# SCH_Octacon_Pico2.net
KiCad netlist of a schematic drawn in EasyEDA
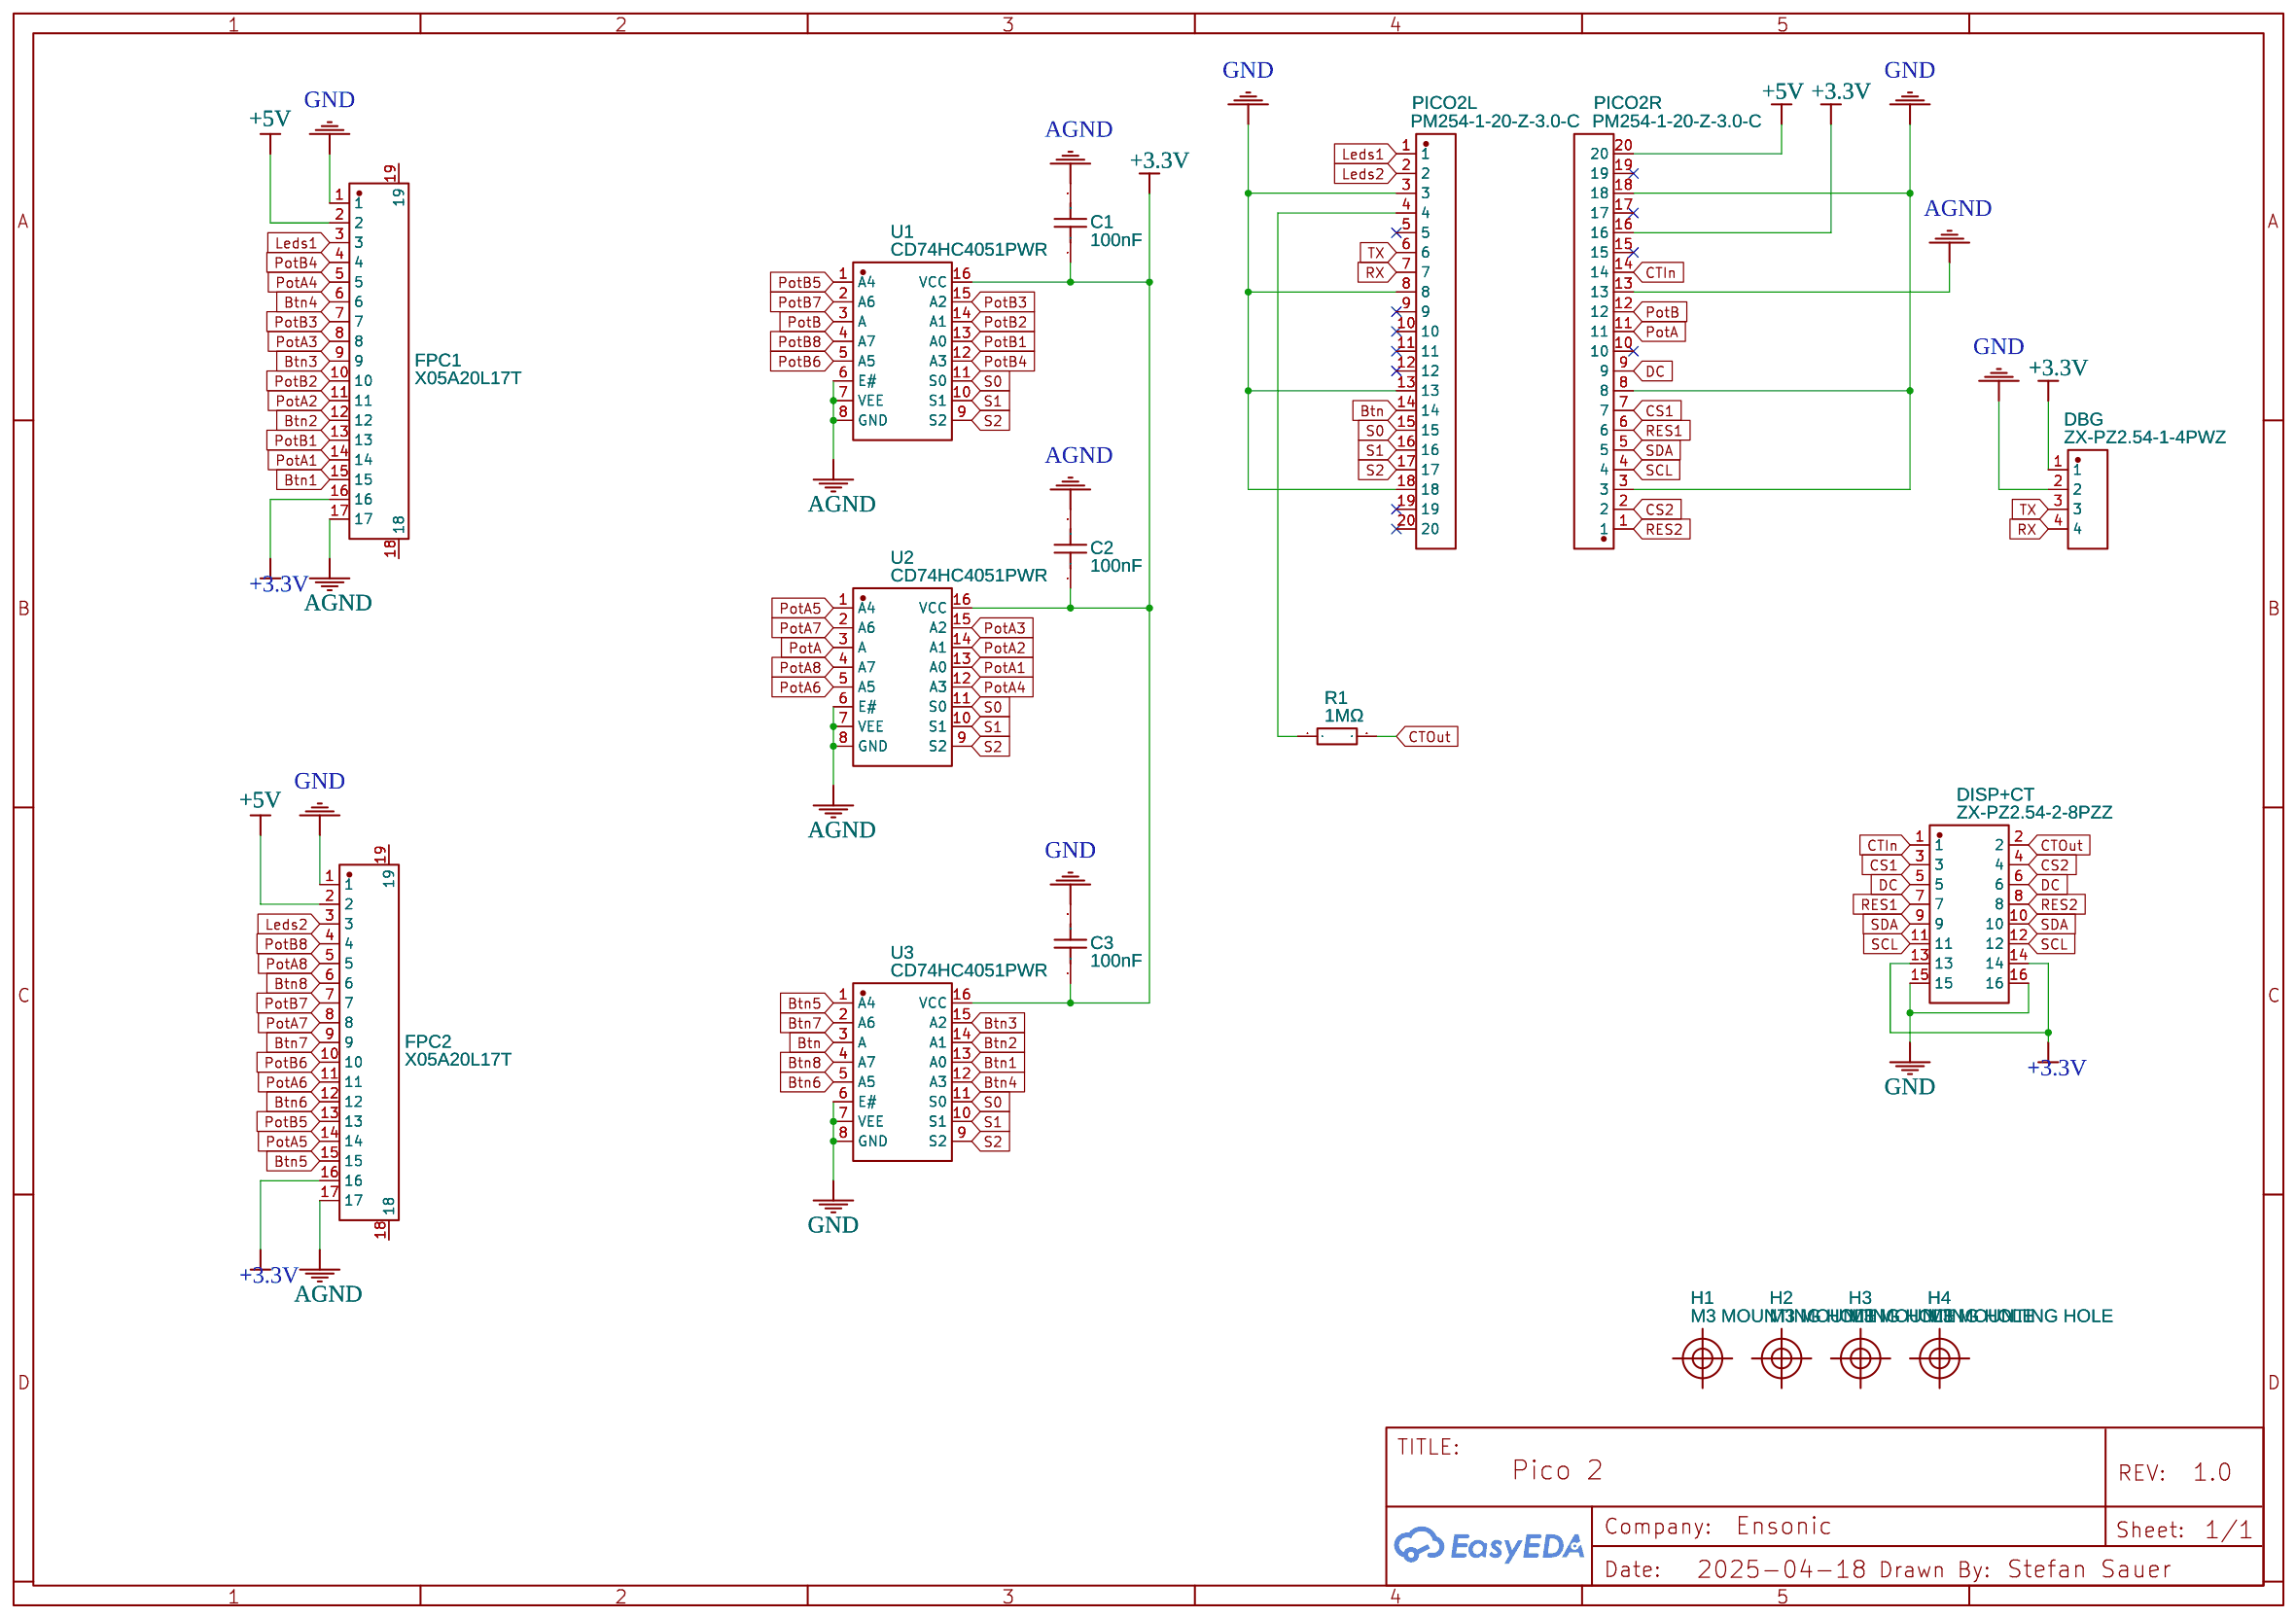
[diagram p0: schematic sheet]

(export (version "E")
  (design (tool "Eeschema 10.0.6"))
  (components
    (comp (ref "C1")
      (value "100nF")
      (fields
        (field (name "Manufacturer Part") "CT41G-0402-2X1-16V-0.1μF-K(N)")
        (field (name "Manufacturer") "TORCH(火炬)")
      )
      (libsource (lib "") (part "CT41G-0402-2X1-16V-0.1μF-K(N)"))
    )
    (comp (ref "C2")
      (value "100nF")
      (fields
        (field (name "Manufacturer Part") "CT41G-0402-2X1-16V-0.1μF-K(N)")
        (field (name "Manufacturer") "TORCH(火炬)")
      )
      (libsource (lib "") (part "CT41G-0402-2X1-16V-0.1μF-K(N)"))
    )
    (comp (ref "C3")
      (value "100nF")
      (fields
        (field (name "Manufacturer Part") "CT41G-0402-2X1-16V-0.1μF-K(N)")
        (field (name "Manufacturer") "TORCH(火炬)")
      )
      (libsource (lib "") (part "CT41G-0402-2X1-16V-0.1μF-K(N)"))
    )
    (comp (ref "DBG")
      (value "ZX-PZ2.54-1-4PWZ")
      (fields (field (name "Manufacturer") "Megastar(兆星)"))
      (libsource (lib "") (part "ZX-PZ2.54-1-4PWZ"))
    )
    (comp (ref "DISP+CT")
      (value "ZX-PZ2.54-2-8PZZ")
      (fields (field (name "Manufacturer") "Megastar(兆星)"))
      (libsource (lib "") (part "ZX-PZ2.54-2-8PZZ"))
    )
    (comp (ref "FPC1")
      (value "X05A20L17T")
      (fields (field (name "Manufacturer") "XKB Connection(中国星坤)"))
      (libsource (lib "") (part "X05A20L17T"))
    )
    (comp (ref "FPC2")
      (value "X05A20L17T")
      (fields (field (name "Manufacturer") "XKB Connection(中国星坤)"))
      (libsource (lib "") (part "X05A20L17T"))
    )
    (comp (ref "H1")
      (value "M3 MOUNTING HOLE")
      (fields (field (name "Manufacturer Part") "M3 Mounting Hole"))
      (libsource (lib "") (part "M3 MOUNTING HOLE"))
    )
    (comp (ref "H2")
      (value "M3 MOUNTING HOLE")
      (fields (field (name "Manufacturer Part") "M3 Mounting Hole"))
      (libsource (lib "") (part "M3 MOUNTING HOLE"))
    )
    (comp (ref "H3")
      (value "M3 MOUNTING HOLE")
      (fields (field (name "Manufacturer Part") "M3 Mounting Hole"))
      (libsource (lib "") (part "M3 MOUNTING HOLE"))
    )
    (comp (ref "H4")
      (value "M3 MOUNTING HOLE")
      (fields (field (name "Manufacturer Part") "M3 Mounting Hole"))
      (libsource (lib "") (part "M3 MOUNTING HOLE"))
    )
    (comp (ref "PICO2L")
      (value "PM254-1-20-Z-3.0-C")
      (fields (field (name "Manufacturer") "HCTL(华灿天禄)"))
      (libsource (lib "") (part "PM254-1-20-Z-3.0-C_1"))
    )
    (comp (ref "PICO2R")
      (value "PM254-1-20-Z-3.0-C")
      (fields (field (name "Manufacturer") "HCTL(华灿天禄)"))
      (libsource (lib "") (part "PM254-1-20-Z-3.0-C"))
    )
    (comp (ref "R1")
      (value "1MΩ")
      (fields
        (field (name "Manufacturer Part") "0805W8F1004T5E")
        (field (name "Manufacturer") "UNI-ROYAL(厚声)")
      )
      (libsource (lib "") (part "0805W8F1004T5E"))
    )
    (comp (ref "U1")
      (value "CD74HC4051PWR")
      (fields (field (name "Manufacturer") "TI(德州仪器)"))
      (libsource (lib "") (part "CD74HC4051PWR"))
    )
    (comp (ref "U2")
      (value "CD74HC4051PWR")
      (fields (field (name "Manufacturer") "TI(德州仪器)"))
      (libsource (lib "") (part "CD74HC4051PWR"))
    )
    (comp (ref "U3")
      (value "CD74HC4051PWR")
      (fields (field (name "Manufacturer") "TI(德州仪器)"))
      (libsource (lib "") (part "CD74HC4051PWR"))
    )
  )
  (nets
    (net (code "1") (name "+3.3V") (class "Default")
      (node (ref "C1") (pin "1") (pinfunction "1_1") (pintype "unspecified"))
      (node (ref "C2") (pin "1") (pinfunction "1_1") (pintype "unspecified"))
      (node (ref "C3") (pin "1") (pinfunction "1_1") (pintype "unspecified"))
      (node (ref "DBG") (pin "1") (pinfunction "1_1") (pintype "unspecified"))
      (node (ref "DISP+CT") (pin "13") (pinfunction "13_13") (pintype "unspecified"))
      (node (ref "DISP+CT") (pin "14") (pinfunction "14_14") (pintype "unspecified"))
      (node (ref "FPC1") (pin "16") (pinfunction "16_16") (pintype "unspecified"))
      (node (ref "FPC2") (pin "16") (pinfunction "16_16") (pintype "unspecified"))
      (node (ref "PICO2R") (pin "16") (pinfunction "16_16") (pintype "unspecified"))
      (node (ref "U1") (pin "16") (pinfunction "VCC_16") (pintype "unspecified"))
      (node (ref "U2") (pin "16") (pinfunction "VCC_16") (pintype "unspecified"))
      (node (ref "U3") (pin "16") (pinfunction "VCC_16") (pintype "unspecified"))
    )
    (net (code "2") (name "+5V") (class "Default")
      (node (ref "FPC1") (pin "2") (pinfunction "2_2") (pintype "unspecified"))
      (node (ref "FPC2") (pin "2") (pinfunction "2_2") (pintype "unspecified"))
      (node (ref "PICO2R") (pin "20") (pinfunction "20_20") (pintype "unspecified"))
    )
    (net (code "3") (name "AGND") (class "Default")
      (node (ref "C1") (pin "2") (pinfunction "2_2") (pintype "unspecified"))
      (node (ref "C2") (pin "2") (pinfunction "2_2") (pintype "unspecified"))
      (node (ref "FPC1") (pin "17") (pinfunction "17_17") (pintype "unspecified"))
      (node (ref "FPC2") (pin "17") (pinfunction "17_17") (pintype "unspecified"))
      (node (ref "PICO2R") (pin "13") (pinfunction "13_13") (pintype "unspecified"))
      (node (ref "U1") (pin "6") (pinfunction "E#_6") (pintype "unspecified"))
      (node (ref "U1") (pin "7") (pinfunction "VEE_7") (pintype "unspecified"))
      (node (ref "U1") (pin "8") (pinfunction "GND_8") (pintype "unspecified"))
      (node (ref "U2") (pin "6") (pinfunction "E#_6") (pintype "unspecified"))
      (node (ref "U2") (pin "7") (pinfunction "VEE_7") (pintype "unspecified"))
      (node (ref "U2") (pin "8") (pinfunction "GND_8") (pintype "unspecified"))
    )
    (net (code "4") (name "Btn") (class "Default")
      (node (ref "PICO2L") (pin "14") (pinfunction "14_14") (pintype "unspecified"))
      (node (ref "U3") (pin "3") (pinfunction "A_3") (pintype "unspecified"))
    )
    (net (code "5") (name "Btn1") (class "Default")
      (node (ref "FPC1") (pin "15") (pinfunction "15_15") (pintype "unspecified"))
      (node (ref "U3") (pin "13") (pinfunction "A0_13") (pintype "unspecified"))
    )
    (net (code "6") (name "Btn2") (class "Default")
      (node (ref "FPC1") (pin "12") (pinfunction "12_12") (pintype "unspecified"))
      (node (ref "U3") (pin "14") (pinfunction "A1_14") (pintype "unspecified"))
    )
    (net (code "7") (name "Btn3") (class "Default")
      (node (ref "FPC1") (pin "9") (pinfunction "9_9") (pintype "unspecified"))
      (node (ref "U3") (pin "15") (pinfunction "A2_15") (pintype "unspecified"))
    )
    (net (code "8") (name "Btn4") (class "Default")
      (node (ref "FPC1") (pin "6") (pinfunction "6_6") (pintype "unspecified"))
      (node (ref "U3") (pin "12") (pinfunction "A3_12") (pintype "unspecified"))
    )
    (net (code "9") (name "Btn5") (class "Default")
      (node (ref "FPC2") (pin "15") (pinfunction "15_15") (pintype "unspecified"))
      (node (ref "U3") (pin "1") (pinfunction "A4_1") (pintype "unspecified"))
    )
    (net (code "10") (name "Btn6") (class "Default")
      (node (ref "FPC2") (pin "12") (pinfunction "12_12") (pintype "unspecified"))
      (node (ref "U3") (pin "5") (pinfunction "A5_5") (pintype "unspecified"))
    )
    (net (code "11") (name "Btn7") (class "Default")
      (node (ref "FPC2") (pin "9") (pinfunction "9_9") (pintype "unspecified"))
      (node (ref "U3") (pin "2") (pinfunction "A6_2") (pintype "unspecified"))
    )
    (net (code "12") (name "Btn8") (class "Default")
      (node (ref "FPC2") (pin "6") (pinfunction "6_6") (pintype "unspecified"))
      (node (ref "U3") (pin "4") (pinfunction "A7_4") (pintype "unspecified"))
    )
    (net (code "13") (name "CS1") (class "Default")
      (node (ref "DISP+CT") (pin "3") (pinfunction "3_3") (pintype "unspecified"))
      (node (ref "PICO2R") (pin "7") (pinfunction "7_7") (pintype "unspecified"))
    )
    (net (code "14") (name "CS2") (class "Default")
      (node (ref "DISP+CT") (pin "4") (pinfunction "4_4") (pintype "unspecified"))
      (node (ref "PICO2R") (pin "2") (pinfunction "2_2") (pintype "unspecified"))
    )
    (net (code "15") (name "CTIn") (class "Default")
      (node (ref "DISP+CT") (pin "1") (pinfunction "1_1") (pintype "unspecified"))
      (node (ref "PICO2R") (pin "14") (pinfunction "14_14") (pintype "unspecified"))
    )
    (net (code "16") (name "CTOut") (class "Default")
      (node (ref "DISP+CT") (pin "2") (pinfunction "2_2") (pintype "unspecified"))
      (node (ref "R1") (pin "2") (pinfunction "2_2") (pintype "input"))
    )
    (net (code "17") (name "DC") (class "Default")
      (node (ref "DISP+CT") (pin "5") (pinfunction "5_5") (pintype "unspecified"))
      (node (ref "DISP+CT") (pin "6") (pinfunction "6_6") (pintype "unspecified"))
      (node (ref "PICO2R") (pin "9") (pinfunction "9_9") (pintype "unspecified"))
    )
    (net (code "18") (name "GND") (class "Default")
      (node (ref "C3") (pin "2") (pinfunction "2_2") (pintype "unspecified"))
      (node (ref "DBG") (pin "2") (pinfunction "2_2") (pintype "unspecified"))
      (node (ref "DISP+CT") (pin "15") (pinfunction "15_15") (pintype "unspecified"))
      (node (ref "DISP+CT") (pin "16") (pinfunction "16_16") (pintype "unspecified"))
      (node (ref "FPC1") (pin "1") (pinfunction "1_1") (pintype "unspecified"))
      (node (ref "FPC2") (pin "1") (pinfunction "1_1") (pintype "unspecified"))
      (node (ref "PICO2L") (pin "13") (pinfunction "13_13") (pintype "unspecified"))
      (node (ref "PICO2L") (pin "18") (pinfunction "18_18") (pintype "unspecified"))
      (node (ref "PICO2L") (pin "3") (pinfunction "3_3") (pintype "unspecified"))
      (node (ref "PICO2L") (pin "8") (pinfunction "8_8") (pintype "unspecified"))
      (node (ref "PICO2R") (pin "18") (pinfunction "18_18") (pintype "unspecified"))
      (node (ref "PICO2R") (pin "3") (pinfunction "3_3") (pintype "unspecified"))
      (node (ref "PICO2R") (pin "8") (pinfunction "8_8") (pintype "unspecified"))
      (node (ref "U3") (pin "6") (pinfunction "E#_6") (pintype "unspecified"))
      (node (ref "U3") (pin "7") (pinfunction "VEE_7") (pintype "unspecified"))
      (node (ref "U3") (pin "8") (pinfunction "GND_8") (pintype "unspecified"))
    )
    (net (code "19") (name "Leds1") (class "Default")
      (node (ref "FPC1") (pin "3") (pinfunction "3_3") (pintype "unspecified"))
      (node (ref "PICO2L") (pin "1") (pinfunction "1_1") (pintype "unspecified"))
    )
    (net (code "20") (name "Leds2") (class "Default")
      (node (ref "FPC2") (pin "3") (pinfunction "3_3") (pintype "unspecified"))
      (node (ref "PICO2L") (pin "2") (pinfunction "2_2") (pintype "unspecified"))
    )
    (net (code "21") (name "Net-(PICO2L-Pad4)") (class "Default")
      (node (ref "PICO2L") (pin "4") (pinfunction "4_4") (pintype "unspecified"))
      (node (ref "R1") (pin "1") (pinfunction "1_1") (pintype "input"))
    )
    (net (code "22") (name "PotA") (class "Default")
      (node (ref "PICO2R") (pin "11") (pinfunction "11_11") (pintype "unspecified"))
      (node (ref "U2") (pin "3") (pinfunction "A_3") (pintype "unspecified"))
    )
    (net (code "23") (name "PotA1") (class "Default")
      (node (ref "FPC1") (pin "14") (pinfunction "14_14") (pintype "unspecified"))
      (node (ref "U2") (pin "13") (pinfunction "A0_13") (pintype "unspecified"))
    )
    (net (code "24") (name "PotA2") (class "Default")
      (node (ref "FPC1") (pin "11") (pinfunction "11_11") (pintype "unspecified"))
      (node (ref "U2") (pin "14") (pinfunction "A1_14") (pintype "unspecified"))
    )
    (net (code "25") (name "PotA3") (class "Default")
      (node (ref "FPC1") (pin "8") (pinfunction "8_8") (pintype "unspecified"))
      (node (ref "U2") (pin "15") (pinfunction "A2_15") (pintype "unspecified"))
    )
    (net (code "26") (name "PotA4") (class "Default")
      (node (ref "FPC1") (pin "5") (pinfunction "5_5") (pintype "unspecified"))
      (node (ref "U2") (pin "12") (pinfunction "A3_12") (pintype "unspecified"))
    )
    (net (code "27") (name "PotA5") (class "Default")
      (node (ref "FPC2") (pin "14") (pinfunction "14_14") (pintype "unspecified"))
      (node (ref "U2") (pin "1") (pinfunction "A4_1") (pintype "unspecified"))
    )
    (net (code "28") (name "PotA6") (class "Default")
      (node (ref "FPC2") (pin "11") (pinfunction "11_11") (pintype "unspecified"))
      (node (ref "U2") (pin "5") (pinfunction "A5_5") (pintype "unspecified"))
    )
    (net (code "29") (name "PotA7") (class "Default")
      (node (ref "FPC2") (pin "8") (pinfunction "8_8") (pintype "unspecified"))
      (node (ref "U2") (pin "2") (pinfunction "A6_2") (pintype "unspecified"))
    )
    (net (code "30") (name "PotA8") (class "Default")
      (node (ref "FPC2") (pin "5") (pinfunction "5_5") (pintype "unspecified"))
      (node (ref "U2") (pin "4") (pinfunction "A7_4") (pintype "unspecified"))
    )
    (net (code "31") (name "PotB") (class "Default")
      (node (ref "PICO2R") (pin "12") (pinfunction "12_12") (pintype "unspecified"))
      (node (ref "U1") (pin "3") (pinfunction "A_3") (pintype "unspecified"))
    )
    (net (code "32") (name "PotB1") (class "Default")
      (node (ref "FPC1") (pin "13") (pinfunction "13_13") (pintype "unspecified"))
      (node (ref "U1") (pin "13") (pinfunction "A0_13") (pintype "unspecified"))
    )
    (net (code "33") (name "PotB2") (class "Default")
      (node (ref "FPC1") (pin "10") (pinfunction "10_10") (pintype "unspecified"))
      (node (ref "U1") (pin "14") (pinfunction "A1_14") (pintype "unspecified"))
    )
    (net (code "34") (name "PotB3") (class "Default")
      (node (ref "FPC1") (pin "7") (pinfunction "7_7") (pintype "unspecified"))
      (node (ref "U1") (pin "15") (pinfunction "A2_15") (pintype "unspecified"))
    )
    (net (code "35") (name "PotB4") (class "Default")
      (node (ref "FPC1") (pin "4") (pinfunction "4_4") (pintype "unspecified"))
      (node (ref "U1") (pin "12") (pinfunction "A3_12") (pintype "unspecified"))
    )
    (net (code "36") (name "PotB5") (class "Default")
      (node (ref "FPC2") (pin "13") (pinfunction "13_13") (pintype "unspecified"))
      (node (ref "U1") (pin "1") (pinfunction "A4_1") (pintype "unspecified"))
    )
    (net (code "37") (name "PotB6") (class "Default")
      (node (ref "FPC2") (pin "10") (pinfunction "10_10") (pintype "unspecified"))
      (node (ref "U1") (pin "5") (pinfunction "A5_5") (pintype "unspecified"))
    )
    (net (code "38") (name "PotB7") (class "Default")
      (node (ref "FPC2") (pin "7") (pinfunction "7_7") (pintype "unspecified"))
      (node (ref "U1") (pin "2") (pinfunction "A6_2") (pintype "unspecified"))
    )
    (net (code "39") (name "PotB8") (class "Default")
      (node (ref "FPC2") (pin "4") (pinfunction "4_4") (pintype "unspecified"))
      (node (ref "U1") (pin "4") (pinfunction "A7_4") (pintype "unspecified"))
    )
    (net (code "40") (name "RES1") (class "Default")
      (node (ref "DISP+CT") (pin "7") (pinfunction "7_7") (pintype "unspecified"))
      (node (ref "PICO2R") (pin "6") (pinfunction "6_6") (pintype "unspecified"))
    )
    (net (code "41") (name "RES2") (class "Default")
      (node (ref "DISP+CT") (pin "8") (pinfunction "8_8") (pintype "unspecified"))
      (node (ref "PICO2R") (pin "1") (pinfunction "1_1") (pintype "unspecified"))
    )
    (net (code "42") (name "RX") (class "Default")
      (node (ref "DBG") (pin "4") (pinfunction "4_4") (pintype "unspecified"))
      (node (ref "PICO2L") (pin "7") (pinfunction "7_7") (pintype "unspecified"))
    )
    (net (code "43") (name "S0") (class "Default")
      (node (ref "PICO2L") (pin "15") (pinfunction "15_15") (pintype "unspecified"))
      (node (ref "U1") (pin "11") (pinfunction "S0_11") (pintype "unspecified"))
      (node (ref "U2") (pin "11") (pinfunction "S0_11") (pintype "unspecified"))
      (node (ref "U3") (pin "11") (pinfunction "S0_11") (pintype "unspecified"))
    )
    (net (code "44") (name "S1") (class "Default")
      (node (ref "PICO2L") (pin "16") (pinfunction "16_16") (pintype "unspecified"))
      (node (ref "U1") (pin "10") (pinfunction "S1_10") (pintype "unspecified"))
      (node (ref "U2") (pin "10") (pinfunction "S1_10") (pintype "unspecified"))
      (node (ref "U3") (pin "10") (pinfunction "S1_10") (pintype "unspecified"))
    )
    (net (code "45") (name "S2") (class "Default")
      (node (ref "PICO2L") (pin "17") (pinfunction "17_17") (pintype "unspecified"))
      (node (ref "U1") (pin "9") (pinfunction "S2_9") (pintype "unspecified"))
      (node (ref "U2") (pin "9") (pinfunction "S2_9") (pintype "unspecified"))
      (node (ref "U3") (pin "9") (pinfunction "S2_9") (pintype "unspecified"))
    )
    (net (code "46") (name "SCL") (class "Default")
      (node (ref "DISP+CT") (pin "11") (pinfunction "11_11") (pintype "unspecified"))
      (node (ref "DISP+CT") (pin "12") (pinfunction "12_12") (pintype "unspecified"))
      (node (ref "PICO2R") (pin "4") (pinfunction "4_4") (pintype "unspecified"))
    )
    (net (code "47") (name "SDA") (class "Default")
      (node (ref "DISP+CT") (pin "10") (pinfunction "10_10") (pintype "unspecified"))
      (node (ref "DISP+CT") (pin "9") (pinfunction "9_9") (pintype "unspecified"))
      (node (ref "PICO2R") (pin "5") (pinfunction "5_5") (pintype "unspecified"))
    )
    (net (code "48") (name "TX") (class "Default")
      (node (ref "DBG") (pin "3") (pinfunction "3_3") (pintype "unspecified"))
      (node (ref "PICO2L") (pin "6") (pinfunction "6_6") (pintype "unspecified"))
    )
    (net (code "49") (name "unconnected-(FPC1-Pad18)") (class "Default")
      (node (ref "FPC1") (pin "18") (pinfunction "18_18") (pintype "unspecified"))
    )
    (net (code "50") (name "unconnected-(FPC1-Pad19)") (class "Default")
      (node (ref "FPC1") (pin "19") (pinfunction "19_19") (pintype "unspecified"))
    )
    (net (code "51") (name "unconnected-(FPC2-Pad18)") (class "Default")
      (node (ref "FPC2") (pin "18") (pinfunction "18_18") (pintype "unspecified"))
    )
    (net (code "52") (name "unconnected-(FPC2-Pad19)") (class "Default")
      (node (ref "FPC2") (pin "19") (pinfunction "19_19") (pintype "unspecified"))
    )
    (net (code "53") (name "unconnected-(PICO2L-Pad5)") (class "Default")
      (node (ref "PICO2L") (pin "5") (pinfunction "5_5") (pintype "unspecified+no_connect"))
    )
    (net (code "54") (name "unconnected-(PICO2L-Pad9)") (class "Default")
      (node (ref "PICO2L") (pin "9") (pinfunction "9_9") (pintype "unspecified+no_connect"))
    )
    (net (code "55") (name "unconnected-(PICO2L-Pad10)") (class "Default")
      (node (ref "PICO2L") (pin "10") (pinfunction "10_10") (pintype "unspecified+no_connect"))
    )
    (net (code "56") (name "unconnected-(PICO2L-Pad11)") (class "Default")
      (node (ref "PICO2L") (pin "11") (pinfunction "11_11") (pintype "unspecified+no_connect"))
    )
    (net (code "57") (name "unconnected-(PICO2L-Pad12)") (class "Default")
      (node (ref "PICO2L") (pin "12") (pinfunction "12_12") (pintype "unspecified+no_connect"))
    )
    (net (code "58") (name "unconnected-(PICO2L-Pad19)") (class "Default")
      (node (ref "PICO2L") (pin "19") (pinfunction "19_19") (pintype "unspecified+no_connect"))
    )
    (net (code "59") (name "unconnected-(PICO2L-Pad20)") (class "Default")
      (node (ref "PICO2L") (pin "20") (pinfunction "20_20") (pintype "unspecified+no_connect"))
    )
    (net (code "60") (name "unconnected-(PICO2R-Pad10)") (class "Default")
      (node (ref "PICO2R") (pin "10") (pinfunction "10_10") (pintype "unspecified+no_connect"))
    )
    (net (code "61") (name "unconnected-(PICO2R-Pad15)") (class "Default")
      (node (ref "PICO2R") (pin "15") (pinfunction "15_15") (pintype "unspecified+no_connect"))
    )
    (net (code "62") (name "unconnected-(PICO2R-Pad17)") (class "Default")
      (node (ref "PICO2R") (pin "17") (pinfunction "17_17") (pintype "unspecified+no_connect"))
    )
    (net (code "63") (name "unconnected-(PICO2R-Pad19)") (class "Default")
      (node (ref "PICO2R") (pin "19") (pinfunction "19_19") (pintype "unspecified+no_connect"))
    )
  )
)
